# 12V_out_driver.net
KiCad netlist of a schematic drawn in Altium Designer
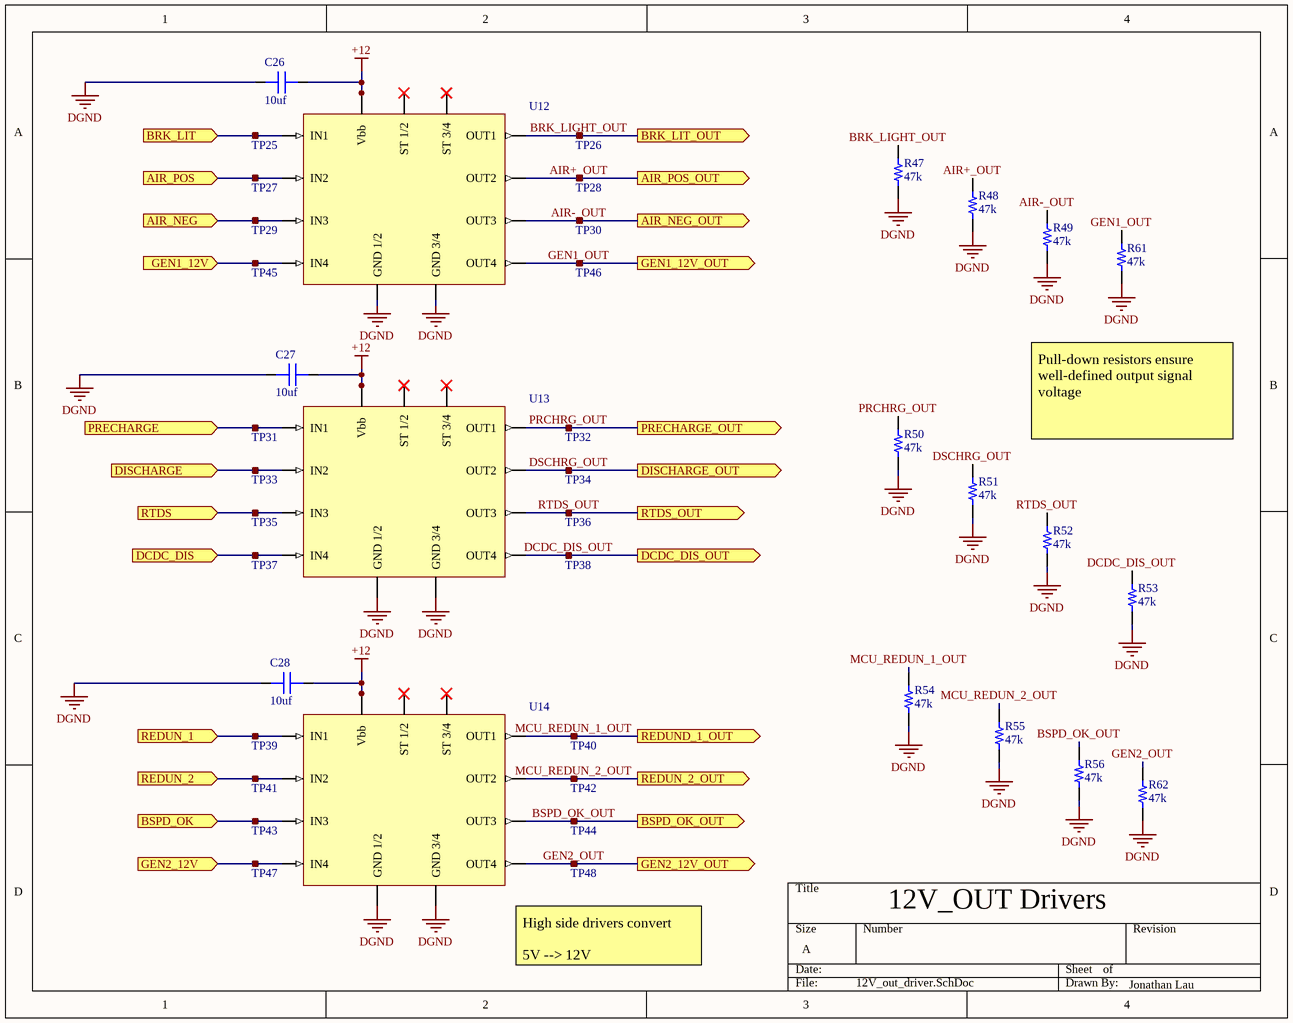
[diagram p0: 12V_out_driver.SchDoc]

(export (version "E")
  (design (tool "Eeschema 10.0.6"))
  (components
    (comp (ref "C26")
      (value "10uf")
      (footprint "CAP 0603/1608")
      (fields
        (field (name "Comment") "Capacitor MLCC 10uf 16V CAP 0603/1608")
        (field (name "CREATED_BY") "Nick Mah")
      )
      (libsource (lib "Altium-Lib") (part "Capacitor"))
    )
    (comp (ref "C27")
      (value "10uf")
      (footprint "CAP 0603/1608")
      (fields
        (field (name "Comment") "Capacitor MLCC 10uf 16V CAP 0603/1608")
        (field (name "CREATED_BY") "Nick Mah")
      )
      (libsource (lib "Altium-Lib") (part "Capacitor"))
    )
    (comp (ref "C28")
      (value "10uf")
      (footprint "CAP 0603/1608")
      (fields
        (field (name "Comment") "Capacitor MLCC 10uf 16V CAP 0603/1608")
        (field (name "CREATED_BY") "Nick Mah")
      )
      (libsource (lib "Altium-Lib") (part "Capacitor"))
    )
    (comp (ref "R47")
      (value "47k")
      (footprint "RES 0805/2012")
      (fields
        (field (name "TOLERANCE") "5%")
        (field (name "POWER") "1/4W")
        (field (name "Comment") "Resistor 47k 0805 1/4W 5%")
        (field (name "CREATED_BY") "Nick Mah")
      )
      (libsource (lib "Altium-Lib") (part "Resistor"))
    )
    (comp (ref "R48")
      (value "47k")
      (footprint "RES 0805/2012")
      (fields
        (field (name "TOLERANCE") "5%")
        (field (name "POWER") "1/4W")
        (field (name "Comment") "Resistor 47k 0805 1/4W 5%")
        (field (name "CREATED_BY") "Nick Mah")
      )
      (libsource (lib "Altium-Lib") (part "Resistor"))
    )
    (comp (ref "R49")
      (value "47k")
      (footprint "RES 0805/2012")
      (fields
        (field (name "TOLERANCE") "5%")
        (field (name "POWER") "1/4W")
        (field (name "Comment") "Resistor 47k 0805 1/4W 5%")
        (field (name "CREATED_BY") "Nick Mah")
      )
      (libsource (lib "Altium-Lib") (part "Resistor"))
    )
    (comp (ref "R50")
      (value "47k")
      (footprint "RES 0805/2012")
      (fields
        (field (name "TOLERANCE") "5%")
        (field (name "POWER") "1/4W")
        (field (name "Comment") "Resistor 47k 0805 1/4W 5%")
        (field (name "CREATED_BY") "Nick Mah")
      )
      (libsource (lib "Altium-Lib") (part "Resistor"))
    )
    (comp (ref "R51")
      (value "47k")
      (footprint "RES 0805/2012")
      (fields
        (field (name "TOLERANCE") "5%")
        (field (name "POWER") "1/4W")
        (field (name "Comment") "Resistor 47k 0805 1/4W 5%")
        (field (name "CREATED_BY") "Nick Mah")
      )
      (libsource (lib "Altium-Lib") (part "Resistor"))
    )
    (comp (ref "R52")
      (value "47k")
      (footprint "RES 0805/2012")
      (fields
        (field (name "TOLERANCE") "5%")
        (field (name "POWER") "1/4W")
        (field (name "Comment") "Resistor 47k 0805 1/4W 5%")
        (field (name "CREATED_BY") "Nick Mah")
      )
      (libsource (lib "Altium-Lib") (part "Resistor"))
    )
    (comp (ref "R53")
      (value "47k")
      (footprint "RES 0805/2012")
      (fields
        (field (name "TOLERANCE") "5%")
        (field (name "POWER") "1/4W")
        (field (name "Comment") "Resistor 47k 0805 1/4W 5%")
        (field (name "CREATED_BY") "Nick Mah")
      )
      (libsource (lib "Altium-Lib") (part "Resistor"))
    )
    (comp (ref "R54")
      (value "47k")
      (footprint "RES 0805/2012")
      (fields
        (field (name "TOLERANCE") "5%")
        (field (name "POWER") "1/4W")
        (field (name "Comment") "Resistor 47k 0805 1/4W 5%")
        (field (name "CREATED_BY") "Nick Mah")
      )
      (libsource (lib "Altium-Lib") (part "Resistor"))
    )
    (comp (ref "R55")
      (value "47k")
      (footprint "RES 0805/2012")
      (fields
        (field (name "TOLERANCE") "5%")
        (field (name "POWER") "1/4W")
        (field (name "Comment") "Resistor 47k 0805 1/4W 5%")
        (field (name "CREATED_BY") "Nick Mah")
      )
      (libsource (lib "Altium-Lib") (part "Resistor"))
    )
    (comp (ref "R56")
      (value "47k")
      (footprint "RES 0805/2012")
      (fields
        (field (name "TOLERANCE") "5%")
        (field (name "POWER") "1/4W")
        (field (name "Comment") "Resistor 47k 0805 1/4W 5%")
        (field (name "CREATED_BY") "Nick Mah")
      )
      (libsource (lib "Altium-Lib") (part "Resistor"))
    )
    (comp (ref "R61")
      (value "47k")
      (footprint "RES 0805/2012")
      (fields
        (field (name "TOLERANCE") "5%")
        (field (name "POWER") "1/4W")
        (field (name "Comment") "Resistor 47k 0805 1/4W 5%")
        (field (name "CREATED_BY") "Nick Mah")
      )
      (libsource (lib "Altium-Lib") (part "Resistor"))
    )
    (comp (ref "R62")
      (value "47k")
      (footprint "RES 0805/2012")
      (fields
        (field (name "TOLERANCE") "5%")
        (field (name "POWER") "1/4W")
        (field (name "Comment") "Resistor 47k 0805 1/4W 5%")
        (field (name "CREATED_BY") "Nick Mah")
      )
      (libsource (lib "Altium-Lib") (part "Resistor"))
    )
    (comp (ref "TP25") (value "RCU-0C") (footprint "RCU-0C") (libsource (lib "Altium-Lib") (part "RCU-0C")))
    (comp (ref "TP26") (value "RCU-0C") (footprint "RCU-0C") (libsource (lib "Altium-Lib") (part "RCU-0C")))
    (comp (ref "TP27") (value "RCU-0C") (footprint "RCU-0C") (libsource (lib "Altium-Lib") (part "RCU-0C")))
    (comp (ref "TP28") (value "RCU-0C") (footprint "RCU-0C") (libsource (lib "Altium-Lib") (part "RCU-0C")))
    (comp (ref "TP29") (value "RCU-0C") (footprint "RCU-0C") (libsource (lib "Altium-Lib") (part "RCU-0C")))
    (comp (ref "TP30") (value "RCU-0C") (footprint "RCU-0C") (libsource (lib "Altium-Lib") (part "RCU-0C")))
    (comp (ref "TP31") (value "RCU-0C") (footprint "RCU-0C") (libsource (lib "Altium-Lib") (part "RCU-0C")))
    (comp (ref "TP32") (value "RCU-0C") (footprint "RCU-0C") (libsource (lib "Altium-Lib") (part "RCU-0C")))
    (comp (ref "TP33") (value "RCU-0C") (footprint "RCU-0C") (libsource (lib "Altium-Lib") (part "RCU-0C")))
    (comp (ref "TP34") (value "RCU-0C") (footprint "RCU-0C") (libsource (lib "Altium-Lib") (part "RCU-0C")))
    (comp (ref "TP35") (value "RCU-0C") (footprint "RCU-0C") (libsource (lib "Altium-Lib") (part "RCU-0C")))
    (comp (ref "TP36") (value "RCU-0C") (footprint "RCU-0C") (libsource (lib "Altium-Lib") (part "RCU-0C")))
    (comp (ref "TP37") (value "RCU-0C") (footprint "RCU-0C") (libsource (lib "Altium-Lib") (part "RCU-0C")))
    (comp (ref "TP38") (value "RCU-0C") (footprint "RCU-0C") (libsource (lib "Altium-Lib") (part "RCU-0C")))
    (comp (ref "TP39") (value "RCU-0C") (footprint "RCU-0C") (libsource (lib "Altium-Lib") (part "RCU-0C")))
    (comp (ref "TP40") (value "RCU-0C") (footprint "RCU-0C") (libsource (lib "Altium-Lib") (part "RCU-0C")))
    (comp (ref "TP41") (value "RCU-0C") (footprint "RCU-0C") (libsource (lib "Altium-Lib") (part "RCU-0C")))
    (comp (ref "TP42") (value "RCU-0C") (footprint "RCU-0C") (libsource (lib "Altium-Lib") (part "RCU-0C")))
    (comp (ref "TP43") (value "RCU-0C") (footprint "RCU-0C") (libsource (lib "Altium-Lib") (part "RCU-0C")))
    (comp (ref "TP44") (value "RCU-0C") (footprint "RCU-0C") (libsource (lib "Altium-Lib") (part "RCU-0C")))
    (comp (ref "TP45") (value "RCU-0C") (footprint "RCU-0C") (libsource (lib "Altium-Lib") (part "RCU-0C")))
    (comp (ref "TP46") (value "RCU-0C") (footprint "RCU-0C") (libsource (lib "Altium-Lib") (part "RCU-0C")))
    (comp (ref "TP47") (value "RCU-0C") (footprint "RCU-0C") (libsource (lib "Altium-Lib") (part "RCU-0C")))
    (comp (ref "TP48") (value "RCU-0C") (footprint "RCU-0C") (libsource (lib "Altium-Lib") (part "RCU-0C")))
    (comp (ref "U12")
      (value "PG-DSO-20")
      (footprint "PG-DSO-20")
      (description "High Side Driver")
      (fields (field (name "MFRPARTNO") "BTS716GXUMA1"))
      (libsource (lib "Altium-Lib") (part "BTS716G"))
    )
    (comp (ref "U13")
      (value "PG-DSO-20")
      (footprint "PG-DSO-20")
      (description "High Side Driver")
      (fields (field (name "MFRPARTNO") "BTS716GXUMA1"))
      (libsource (lib "Altium-Lib") (part "BTS716G"))
    )
    (comp (ref "U14")
      (value "PG-DSO-20")
      (footprint "PG-DSO-20")
      (description "High Side Driver")
      (fields (field (name "MFRPARTNO") "BTS716GXUMA1"))
      (libsource (lib "Altium-Lib") (part "BTS716G"))
    )
  )
  (nets
    (net (code "1") (name "+12") (class "Default")
      (node (ref "C26") (pin "2") (pinfunction "2_2") (pintype "passive"))
      (node (ref "C27") (pin "2") (pinfunction "2_2") (pintype "passive"))
      (node (ref "C28") (pin "2") (pinfunction "2_2") (pintype "passive"))
      (node (ref "U12") (pin "1") (pinfunction "Vbb_1") (pintype "power_in"))
      (node (ref "U12") (pin "10") (pinfunction "Vbb_10") (pintype "power_in"))
      (node (ref "U12") (pin "11") (pinfunction "Vbb_11") (pintype "power_in"))
      (node (ref "U12") (pin "12") (pinfunction "Vbb_12") (pintype "power_in"))
      (node (ref "U12") (pin "15") (pinfunction "Vbb_15") (pintype "power_in"))
      (node (ref "U12") (pin "16") (pinfunction "Vbb_16") (pintype "power_in"))
      (node (ref "U12") (pin "19") (pinfunction "Vbb_19") (pintype "power_in"))
      (node (ref "U12") (pin "20") (pinfunction "Vbb_20") (pintype "power_in"))
      (node (ref "U13") (pin "1") (pinfunction "Vbb_1") (pintype "power_in"))
      (node (ref "U13") (pin "10") (pinfunction "Vbb_10") (pintype "power_in"))
      (node (ref "U13") (pin "11") (pinfunction "Vbb_11") (pintype "power_in"))
      (node (ref "U13") (pin "12") (pinfunction "Vbb_12") (pintype "power_in"))
      (node (ref "U13") (pin "15") (pinfunction "Vbb_15") (pintype "power_in"))
      (node (ref "U13") (pin "16") (pinfunction "Vbb_16") (pintype "power_in"))
      (node (ref "U13") (pin "19") (pinfunction "Vbb_19") (pintype "power_in"))
      (node (ref "U13") (pin "20") (pinfunction "Vbb_20") (pintype "power_in"))
      (node (ref "U14") (pin "1") (pinfunction "Vbb_1") (pintype "power_in"))
      (node (ref "U14") (pin "10") (pinfunction "Vbb_10") (pintype "power_in"))
      (node (ref "U14") (pin "11") (pinfunction "Vbb_11") (pintype "power_in"))
      (node (ref "U14") (pin "12") (pinfunction "Vbb_12") (pintype "power_in"))
      (node (ref "U14") (pin "15") (pinfunction "Vbb_15") (pintype "power_in"))
      (node (ref "U14") (pin "16") (pinfunction "Vbb_16") (pintype "power_in"))
      (node (ref "U14") (pin "19") (pinfunction "Vbb_19") (pintype "power_in"))
      (node (ref "U14") (pin "20") (pinfunction "Vbb_20") (pintype "power_in"))
    )
    (net (code "2") (name "/AIR+_OUT") (class "Default")
      (node (ref "R48") (pin "2") (pinfunction "2_2") (pintype "passive"))
      (node (ref "TP28") (pin "1") (pintype "passive"))
      (node (ref "U12") (pin "17") (pinfunction "OUT2_17") (pintype "output"))
    )
    (net (code "3") (name "/AIR-_OUT") (class "Default")
      (node (ref "R49") (pin "2") (pinfunction "2_2") (pintype "passive"))
      (node (ref "TP30") (pin "1") (pintype "passive"))
      (node (ref "U12") (pin "14") (pinfunction "OUT3_14") (pintype "output"))
    )
    (net (code "4") (name "/AIR_NEG") (class "Default")
      (node (ref "TP29") (pin "1") (pintype "passive"))
      (node (ref "U12") (pin "7") (pinfunction "IN3_7") (pintype "input"))
    )
    (net (code "5") (name "/AIR_POS") (class "Default")
      (node (ref "TP27") (pin "1") (pintype "passive"))
      (node (ref "U12") (pin "5") (pinfunction "IN2_5") (pintype "input"))
    )
    (net (code "6") (name "/BRK_LIGHT_OUT") (class "Default")
      (node (ref "R47") (pin "2") (pinfunction "2_2") (pintype "passive"))
      (node (ref "TP26") (pin "1") (pintype "passive"))
      (node (ref "U12") (pin "18") (pinfunction "OUT1_18") (pintype "output"))
    )
    (net (code "7") (name "/BRK_LIT") (class "Default")
      (node (ref "TP25") (pin "1") (pintype "passive"))
      (node (ref "U12") (pin "3") (pinfunction "IN1_3") (pintype "input"))
    )
    (net (code "8") (name "/BSPD_OK") (class "Default")
      (node (ref "TP43") (pin "1") (pintype "passive"))
      (node (ref "U14") (pin "7") (pinfunction "IN3_7") (pintype "input"))
    )
    (net (code "9") (name "/BSPD_OK_OUT") (class "Default")
      (node (ref "R56") (pin "2") (pinfunction "2_2") (pintype "passive"))
      (node (ref "TP44") (pin "1") (pintype "passive"))
      (node (ref "U14") (pin "14") (pinfunction "OUT3_14") (pintype "output"))
    )
    (net (code "10") (name "/DCDC_DIS") (class "Default")
      (node (ref "TP37") (pin "1") (pintype "passive"))
      (node (ref "U13") (pin "9") (pinfunction "IN4_9") (pintype "input"))
    )
    (net (code "11") (name "/DCDC_DIS_OUT") (class "Default")
      (node (ref "R53") (pin "2") (pinfunction "2_2") (pintype "passive"))
      (node (ref "TP38") (pin "1") (pintype "passive"))
      (node (ref "U13") (pin "13") (pinfunction "OUT4_13") (pintype "output"))
    )
    (net (code "12") (name "/DISCHARGE") (class "Default")
      (node (ref "TP33") (pin "1") (pintype "passive"))
      (node (ref "U13") (pin "5") (pinfunction "IN2_5") (pintype "input"))
    )
    (net (code "13") (name "/DSCHRG_OUT") (class "Default")
      (node (ref "R51") (pin "2") (pinfunction "2_2") (pintype "passive"))
      (node (ref "TP34") (pin "1") (pintype "passive"))
      (node (ref "U13") (pin "17") (pinfunction "OUT2_17") (pintype "output"))
    )
    (net (code "14") (name "/GEN1_12V") (class "Default")
      (node (ref "TP45") (pin "1") (pintype "passive"))
      (node (ref "U12") (pin "9") (pinfunction "IN4_9") (pintype "input"))
    )
    (net (code "15") (name "/GEN1_OUT") (class "Default")
      (node (ref "R61") (pin "2") (pinfunction "2_2") (pintype "passive"))
      (node (ref "TP46") (pin "1") (pintype "passive"))
      (node (ref "U12") (pin "13") (pinfunction "OUT4_13") (pintype "output"))
    )
    (net (code "16") (name "/GEN2_12V") (class "Default")
      (node (ref "TP47") (pin "1") (pintype "passive"))
      (node (ref "U14") (pin "9") (pinfunction "IN4_9") (pintype "input"))
    )
    (net (code "17") (name "/GEN2_OUT") (class "Default")
      (node (ref "R62") (pin "2") (pinfunction "2_2") (pintype "passive"))
      (node (ref "TP48") (pin "1") (pintype "passive"))
      (node (ref "U14") (pin "13") (pinfunction "OUT4_13") (pintype "output"))
    )
    (net (code "18") (name "/MCU_REDUN_1_OUT") (class "Default")
      (node (ref "R54") (pin "2") (pinfunction "2_2") (pintype "passive"))
      (node (ref "TP40") (pin "1") (pintype "passive"))
      (node (ref "U14") (pin "18") (pinfunction "OUT1_18") (pintype "output"))
    )
    (net (code "19") (name "/MCU_REDUN_2_OUT") (class "Default")
      (node (ref "R55") (pin "2") (pinfunction "2_2") (pintype "passive"))
      (node (ref "TP42") (pin "1") (pintype "passive"))
      (node (ref "U14") (pin "17") (pinfunction "OUT2_17") (pintype "output"))
    )
    (net (code "20") (name "/PRCHRG_OUT") (class "Default")
      (node (ref "R50") (pin "2") (pinfunction "2_2") (pintype "passive"))
      (node (ref "TP32") (pin "1") (pintype "passive"))
      (node (ref "U13") (pin "18") (pinfunction "OUT1_18") (pintype "output"))
    )
    (net (code "21") (name "/PRECHARGE") (class "Default")
      (node (ref "TP31") (pin "1") (pintype "passive"))
      (node (ref "U13") (pin "3") (pinfunction "IN1_3") (pintype "input"))
    )
    (net (code "22") (name "/REDUN_1") (class "Default")
      (node (ref "TP39") (pin "1") (pintype "passive"))
      (node (ref "U14") (pin "3") (pinfunction "IN1_3") (pintype "input"))
    )
    (net (code "23") (name "/REDUN_2") (class "Default")
      (node (ref "TP41") (pin "1") (pintype "passive"))
      (node (ref "U14") (pin "5") (pinfunction "IN2_5") (pintype "input"))
    )
    (net (code "24") (name "/RTDS") (class "Default")
      (node (ref "TP35") (pin "1") (pintype "passive"))
      (node (ref "U13") (pin "7") (pinfunction "IN3_7") (pintype "input"))
    )
    (net (code "25") (name "/RTDS_OUT") (class "Default")
      (node (ref "R52") (pin "2") (pinfunction "2_2") (pintype "passive"))
      (node (ref "TP36") (pin "1") (pintype "passive"))
      (node (ref "U13") (pin "14") (pinfunction "OUT3_14") (pintype "output"))
    )
    (net (code "26") (name "DGND") (class "Default")
      (node (ref "C26") (pin "1") (pinfunction "1_1") (pintype "passive"))
      (node (ref "C27") (pin "1") (pinfunction "1_1") (pintype "passive"))
      (node (ref "C28") (pin "1") (pinfunction "1_1") (pintype "passive"))
      (node (ref "R47") (pin "1") (pinfunction "1_1") (pintype "passive"))
      (node (ref "R48") (pin "1") (pinfunction "1_1") (pintype "passive"))
      (node (ref "R49") (pin "1") (pinfunction "1_1") (pintype "passive"))
      (node (ref "R50") (pin "1") (pinfunction "1_1") (pintype "passive"))
      (node (ref "R51") (pin "1") (pinfunction "1_1") (pintype "passive"))
      (node (ref "R52") (pin "1") (pinfunction "1_1") (pintype "passive"))
      (node (ref "R53") (pin "1") (pinfunction "1_1") (pintype "passive"))
      (node (ref "R54") (pin "1") (pinfunction "1_1") (pintype "passive"))
      (node (ref "R55") (pin "1") (pinfunction "1_1") (pintype "passive"))
      (node (ref "R56") (pin "1") (pinfunction "1_1") (pintype "passive"))
      (node (ref "R61") (pin "1") (pinfunction "1_1") (pintype "passive"))
      (node (ref "R62") (pin "1") (pinfunction "1_1") (pintype "passive"))
      (node (ref "U12") (pin "2") (pinfunction "GND_1/2_2") (pintype "power_in"))
      (node (ref "U12") (pin "6") (pinfunction "GND_3/4_6") (pintype "power_in"))
      (node (ref "U13") (pin "2") (pinfunction "GND_1/2_2") (pintype "power_in"))
      (node (ref "U13") (pin "6") (pinfunction "GND_3/4_6") (pintype "power_in"))
      (node (ref "U14") (pin "2") (pinfunction "GND_1/2_2") (pintype "power_in"))
      (node (ref "U14") (pin "6") (pinfunction "GND_3/4_6") (pintype "power_in"))
    )
    (net (code "27") (name "unconnected-(U12-ST_1{slash}2-Pad4)") (class "Default")
      (node (ref "U12") (pin "4") (pinfunction "ST_1/2_4") (pintype "passive+no_connect"))
    )
    (net (code "28") (name "unconnected-(U12-ST_3{slash}4-Pad8)") (class "Default")
      (node (ref "U12") (pin "8") (pinfunction "ST_3/4_8") (pintype "passive+no_connect"))
    )
    (net (code "29") (name "unconnected-(U13-ST_1{slash}2-Pad4)") (class "Default")
      (node (ref "U13") (pin "4") (pinfunction "ST_1/2_4") (pintype "passive+no_connect"))
    )
    (net (code "30") (name "unconnected-(U13-ST_3{slash}4-Pad8)") (class "Default")
      (node (ref "U13") (pin "8") (pinfunction "ST_3/4_8") (pintype "passive+no_connect"))
    )
    (net (code "31") (name "unconnected-(U14-ST_1{slash}2-Pad4)") (class "Default")
      (node (ref "U14") (pin "4") (pinfunction "ST_1/2_4") (pintype "passive+no_connect"))
    )
    (net (code "32") (name "unconnected-(U14-ST_3{slash}4-Pad8)") (class "Default")
      (node (ref "U14") (pin "8") (pinfunction "ST_3/4_8") (pintype "passive+no_connect"))
    )
  )
)
